# Power.net
KiCad netlist of a schematic drawn in Altium Designer
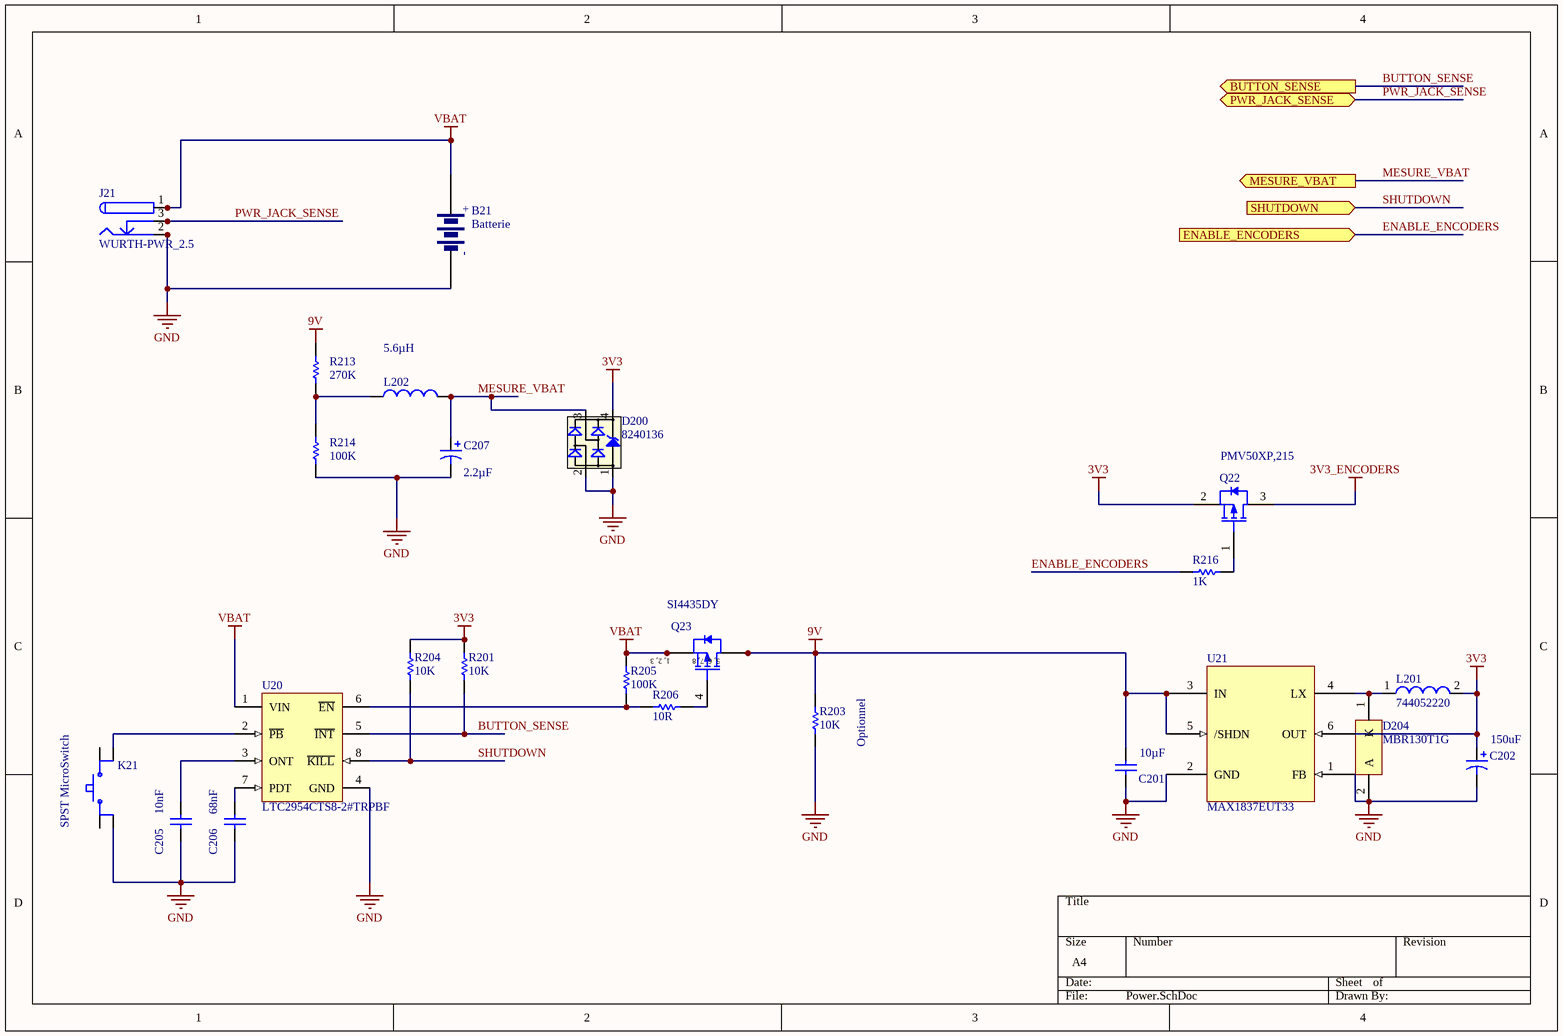
[diagram p0: Power.SchDoc]

(export (version "E")
  (design (tool "Eeschema 10.0.6"))
  (components
    (comp (ref "B21")
      (value "Batterie")
      (footprint "batterie")
      (description "Keystone 1294")
      (libsource (lib "Dumber 2015") (part "Batterie"))
    )
    (comp (ref "C201")
      (value "10µF")
      (footprint "CAPC1206(3216)100_L")
      (description "CAP 10µF 25V ±10% 1206 (3216 Metric) Thickness 1mm SMD")
      (fields (field (name "TOLERANCE") "Â±10%") (field (name "Comment") "CAP 10µF"))
      (libsource (lib "Altium Content Vault") (part "CMP-1037-01131-1"))
    )
    (comp (ref "C202")
      (value "150uF")
      (footprint "B")
      (description "CAP Tantalum, Body B, 150µF / 6.3V")
      (fields (field (name "Comment") "CAP 150µF") (field (name "PUBLISHER") "Altium Limited"))
      (libsource (lib "Vishay Sprague Tantalum Chip Capacitor") (part "194D225X0015B2"))
    )
    (comp (ref "C205")
      (value "10nF")
      (footprint "CAPC1206(3216)170_L")
      (description "CAP 100nF 50V ±10% 1206 (3216 Metric) Thickness 1.7mm SMD")
      (fields (field (name "TOLERANCE") "Â±10%") (field (name "Comment") "CAP 10nf"))
      (libsource (lib "Altium Content Vault") (part "CMP-1037-04201-1"))
    )
    (comp (ref "C206")
      (value "68nF")
      (footprint "CAPC1206(3216)170_L")
      (description "CAP 100nF 50V ±10% 1206 (3216 Metric) Thickness 1.7mm SMD")
      (fields (field (name "TOLERANCE") "Â±10%") (field (name "Comment") "CAP 68nF"))
      (libsource (lib "Altium Content Vault") (part "CMP-1037-04201-1"))
    )
    (comp (ref "C207")
      (value "2.2µF")
      (footprint "B")
      (description "Solid Tantalum Chip Capacitor, Standard T491 Series - Industrial Grade")
      (fields (field (name "Comment") "T491B") (field (name "PUBLISHER") "Altium Limited"))
      (libsource (lib "KEMET Chip Capacitor") (part "T491B"))
    )
    (comp (ref "D200")
      (value "8240136")
      (footprint "SOT143-4L")
      (description "TVS Diode WE-TVS-HS, VRWM=3.3V")
      (fields (field (name "MANUFACTURER") "Wuerth Elektronik"))
      (libsource (lib "Altium Content Vault") (part "WE-TVS-HS-4"))
    )
    (comp (ref "D204")
      (value "MBR130T1G")
      (footprint "ONSC-SOD-123-2-425-04_V")
      (description "Schottky Power Rectifier, 2-Pin SOD-123, Pb-Free, Tape and Reel")
      (fields (field (name "MANUFACTURER") "On Semiconductor"))
      (libsource (lib "Altium Content Vault") (part "CMP-1055-00423-1"))
    )
    (comp (ref "J21")
      (value "WURTH-PWR_2.5")
      (footprint "Wurth_2.5")
      (description "Low Voltage Power Supply Connector")
      (fields (field (name "PUBLISHER") "Altium Limited"))
      (libsource (lib "Dumber 2015") (part "WURTH-PWR_2.5"))
    )
    (comp (ref "K21")
      (value "SPST MicroSwitch")
      (footprint "SPST_MicroSwitch")
      (description "SPST - MicroSwitch")
      (libsource (lib "INSA") (part "SPST MicroSwitch"))
    )
    (comp (ref "L201")
      (value "744052220")
      (footprint "WE-TPC-5818-L")
      (description "SMD Shielded Tiny Power Inductor WE-TPC, L = 22.0 µH")
      (libsource (lib "Altium Content Vault") (part "CMP-0227-00400-1"))
    )
    (comp (ref "L202")
      (value "5.6µH")
      (footprint "1812")
      (description "Inductor SMD")
      (fields (field (name "Comment") "Inductor") (field (name "PUBLISHER") "Altium Limited"))
      (libsource (lib "INSA") (part "Inductor"))
    )
    (comp (ref "Q22")
      (value "PMV50XP,215")
      (footprint "NXP-SOT23_N")
      (description "Single P-Channel Trench MOSFET, -20 V, -55 to 150 degC, 3-Pin SOT23, Tape and Reel")
      (fields (field (name "PARTNUMBER") "PMV65XP,215") (field (name "MANUFACTURER") "NXP Semiconductors"))
      (libsource (lib "Altium Content Vault") (part "CMP-1258-00162-1"))
    )
    (comp (ref "Q23")
      (value "SI4435DY")
      (footprint "SO-8_N")
      (description "P-Channel 30V (D-S) Rated  MOSFET")
      (fields (field (name "PUBLISHER") "Altium Limited"))
      (libsource (lib "Vishay Siliconix Discrete MOSFET") (part "SI4435DY"))
    )
    (comp (ref "R201")
      (value "10K")
      (footprint "RESC1206(3216)_M")
      (description "10K 0.25W 5% 1206 (3216 Metric)  SMD")
      (fields (field (name "POWER") "0.25 W") (field (name "TOLERANCE") "5 %"))
      (libsource (lib "Altium Content Vault") (part "CMP-1014-00098-1"))
    )
    (comp (ref "R203")
      (value "10K")
      (footprint "RESC1206(3216)_M")
      (description "10K 0.25W 5% 1206 (3216 Metric)  SMD")
      (fields (field (name "POWER") "0.25 W") (field (name "TOLERANCE") "5 %"))
      (libsource (lib "Altium Content Vault") (part "CMP-1014-00098-1"))
    )
    (comp (ref "R204")
      (value "10K")
      (footprint "RESC1206(3216)_M")
      (description "10K 0.25W 5% 1206 (3216 Metric)  SMD")
      (fields (field (name "POWER") "0.25 W") (field (name "TOLERANCE") "5 %"))
      (libsource (lib "Altium Content Vault") (part "CMP-1014-00098-1"))
    )
    (comp (ref "R205")
      (value "100K")
      (footprint "RESC1206(3216)_M")
      (description "10K 0.25W 5% 1206 (3216 Metric)  SMD")
      (fields (field (name "POWER") "0.25 W") (field (name "TOLERANCE") "5 %"))
      (libsource (lib "Altium Content Vault") (part "CMP-1014-00098-1"))
    )
    (comp (ref "R206")
      (value "10R")
      (footprint "RESC1206(3216)_M")
      (description "10K 0.25W 5% 1206 (3216 Metric)  SMD")
      (fields (field (name "POWER") "0.25 W") (field (name "TOLERANCE") "5 %"))
      (libsource (lib "Altium Content Vault") (part "CMP-1014-00098-1"))
    )
    (comp (ref "R213")
      (value "270K")
      (footprint "RESC0805(2012)_M")
      (description "270K 0.125W 5% 0805 (2012 Metric)  SMD")
      (fields (field (name "TOLERANCE") "5 %") (field (name "POWER") "0.125 W"))
      (libsource (lib "Altium Content Vault") (part "CMP-1013-00132-1"))
    )
    (comp (ref "R214")
      (value "100K")
      (footprint "RESC1206(3216)_M")
      (description "10K 0.25W 5% 1206 (3216 Metric)  SMD")
      (fields (field (name "POWER") "0.25 W") (field (name "TOLERANCE") "5 %"))
      (libsource (lib "Altium Content Vault") (part "CMP-1014-00098-1"))
    )
    (comp (ref "R216")
      (value "1K")
      (footprint "RESC1206(3216)_M")
      (description "10K 0.25W 5% 1206 (3216 Metric)  SMD")
      (fields (field (name "POWER") "0.25 W") (field (name "TOLERANCE") "5 %"))
      (libsource (lib "Altium Content Vault") (part "CMP-1014-00098-1"))
    )
    (comp (ref "U20")
      (value "LTC2954CTS8-2#TRPBF")
      (footprint "LT-TS8-8-TSOT-23_V")
      (fields (field (name "MANUFACTURER") "Linear Technology"))
      (libsource (lib "Altium Content Vault") (part "LT-LTC2954-2-TS8-8"))
    )
    (comp (ref "U21") (value "MAX1837EUT33") (footprint "SOT23-6") (libsource (lib "INSA") (part "MAX1837")))
  )
  (nets
    (net (code "1") (name "/BUTTON_SENSE") (class "Default")
      (node (ref "R201") (pin "2") (pinfunction "2_2") (pintype "passive"))
      (node (ref "U20") (pin "5") (pinfunction "~{INT}_5") (pintype "open_collector"))
    )
    (net (code "2") (name "/ENABLE_ENCODERS") (class "Default")
      (node (ref "R216") (pin "2") (pinfunction "2_2") (pintype "passive"))
    )
    (net (code "3") (name "/MESURE_VBAT") (class "Default")
      (node (ref "C207") (pin "1") (pinfunction "1_1") (pintype "passive"))
      (node (ref "D200") (pin "3") (pinfunction "I/O2_3") (pintype "passive"))
      (node (ref "L202") (pin "2") (pinfunction "2_2") (pintype "passive"))
    )
    (net (code "4") (name "/PWR_JACK_SENSE") (class "Default")
      (node (ref "J21") (pin "3") (pinfunction "3_3") (pintype "power_in"))
      (node (ref "J21") (pin "3A") (pinfunction "3A_3A") (pintype "power_in"))
      (node (ref "J21") (pin "3B") (pinfunction "3B_3B") (pintype "power_in"))
    )
    (net (code "5") (name "/SHUTDOWN") (class "Default")
      (node (ref "R204") (pin "2") (pinfunction "2_2") (pintype "passive"))
      (node (ref "U20") (pin "8") (pinfunction "~{KILL}_8") (pintype "input"))
    )
    (net (code "6") (name "3V3") (class "Default")
      (node (ref "C202") (pin "1") (pinfunction "1_1") (pintype "passive"))
      (node (ref "D200") (pin "4") (pinfunction "VDD_4") (pintype "passive"))
      (node (ref "L201") (pin "2") (pinfunction "2_2") (pintype "passive"))
      (node (ref "Q22") (pin "2") (pinfunction "S_2") (pintype "passive"))
      (node (ref "R201") (pin "1") (pinfunction "1_1") (pintype "passive"))
      (node (ref "R204") (pin "1") (pinfunction "1_1") (pintype "passive"))
      (node (ref "U21") (pin "6") (pinfunction "OUT_6") (pintype "input"))
    )
    (net (code "7") (name "3V3_ENCODERS") (class "Default")
      (node (ref "Q22") (pin "3") (pinfunction "D_3") (pintype "passive"))
    )
    (net (code "8") (name "9V") (class "Default")
      (node (ref "C201") (pin "2") (pinfunction "2_2") (pintype "passive"))
      (node (ref "Q23") (pin "5") (pinfunction "D_5") (pintype "passive"))
      (node (ref "Q23") (pin "6") (pinfunction "D_6") (pintype "passive"))
      (node (ref "Q23") (pin "7") (pinfunction "D_7") (pintype "passive"))
      (node (ref "Q23") (pin "8") (pinfunction "D_8") (pintype "passive"))
      (node (ref "R203") (pin "1") (pinfunction "1_1") (pintype "passive"))
      (node (ref "R213") (pin "2") (pinfunction "2_2") (pintype "passive"))
      (node (ref "U21") (pin "3") (pinfunction "IN_3") (pintype "power_in"))
      (node (ref "U21") (pin "5") (pinfunction "/SHDN_5") (pintype "input"))
    )
    (net (code "9") (name "GND") (class "Default")
      (node (ref "B21") (pin "V-") (pinfunction "V-_V-") (pintype "passive"))
      (node (ref "C201") (pin "1") (pinfunction "1_1") (pintype "passive"))
      (node (ref "C202") (pin "2") (pinfunction "2_2") (pintype "passive"))
      (node (ref "C205") (pin "1") (pinfunction "1_1") (pintype "passive"))
      (node (ref "C206") (pin "1") (pinfunction "1_1") (pintype "passive"))
      (node (ref "C207") (pin "2") (pinfunction "2_2") (pintype "passive"))
      (node (ref "D200") (pin "1") (pinfunction "GND_1") (pintype "passive"))
      (node (ref "D200") (pin "2") (pinfunction "I/O1_2") (pintype "passive"))
      (node (ref "D204") (pin "2") (pinfunction "A_2") (pintype "passive"))
      (node (ref "J21") (pin "2") (pinfunction "2_2") (pintype "power_in"))
      (node (ref "J21") (pin "2A") (pinfunction "2A_2A") (pintype "power_in"))
      (node (ref "J21") (pin "2B") (pinfunction "2B_2B") (pintype "power_in"))
      (node (ref "K21") (pin "2") (pinfunction "2_2") (pintype "passive"))
      (node (ref "R203") (pin "2") (pinfunction "2_2") (pintype "passive"))
      (node (ref "R214") (pin "2") (pinfunction "2_2") (pintype "passive"))
      (node (ref "U20") (pin "4") (pinfunction "GND_4") (pintype "power_in"))
      (node (ref "U21") (pin "1") (pinfunction "FB_1") (pintype "input"))
      (node (ref "U21") (pin "2") (pinfunction "GND_2") (pintype "power_in"))
    )
    (net (code "10") (name "Net-(D204-K)") (class "Default")
      (node (ref "D204") (pin "1") (pinfunction "K_1") (pintype "passive"))
      (node (ref "L201") (pin "1") (pinfunction "1_1") (pintype "passive"))
      (node (ref "U21") (pin "4") (pinfunction "LX_4") (pintype "power_in"))
    )
    (net (code "11") (name "Net-(L202-Pad1)") (class "Default")
      (node (ref "L202") (pin "1") (pinfunction "1_1") (pintype "passive"))
      (node (ref "R213") (pin "1") (pinfunction "1_1") (pintype "passive"))
      (node (ref "R214") (pin "1") (pinfunction "1_1") (pintype "passive"))
    )
    (net (code "12") (name "Net-(Q22-G)") (class "Default")
      (node (ref "Q22") (pin "1") (pinfunction "G_1") (pintype "passive"))
      (node (ref "R216") (pin "1") (pinfunction "1_1") (pintype "passive"))
    )
    (net (code "13") (name "Net-(Q23-G)") (class "Default")
      (node (ref "Q23") (pin "4") (pinfunction "G_4") (pintype "passive"))
      (node (ref "R206") (pin "1") (pinfunction "1_1") (pintype "passive"))
    )
    (net (code "14") (name "Net-(U20-ONT)") (class "Default")
      (node (ref "C205") (pin "2") (pinfunction "2_2") (pintype "passive"))
      (node (ref "U20") (pin "3") (pinfunction "ONT_3") (pintype "input"))
    )
    (net (code "15") (name "Net-(U20-PDT)") (class "Default")
      (node (ref "C206") (pin "2") (pinfunction "2_2") (pintype "passive"))
      (node (ref "U20") (pin "7") (pinfunction "PDT_7") (pintype "input"))
    )
    (net (code "16") (name "Net-(U20-~{EN})") (class "Default")
      (node (ref "R205") (pin "2") (pinfunction "2_2") (pintype "passive"))
      (node (ref "R206") (pin "2") (pinfunction "2_2") (pintype "passive"))
      (node (ref "U20") (pin "6") (pinfunction "~{EN}_6") (pintype "open_collector"))
    )
    (net (code "17") (name "Net-(U20-~{PB})") (class "Default")
      (node (ref "K21") (pin "4") (pinfunction "4_4") (pintype "passive"))
      (node (ref "U20") (pin "2") (pinfunction "~{PB}_2") (pintype "input"))
    )
    (net (code "18") (name "VBAT") (class "Default")
      (node (ref "B21") (pin "V+") (pinfunction "V+_V+") (pintype "passive"))
      (node (ref "J21") (pin "1") (pinfunction "1_1") (pintype "power_in"))
      (node (ref "J21") (pin "1A") (pinfunction "1A_1A") (pintype "power_in"))
      (node (ref "J21") (pin "1B") (pinfunction "1B_1B") (pintype "power_in"))
      (node (ref "Q23") (pin "1") (pinfunction "S_1") (pintype "passive"))
      (node (ref "Q23") (pin "2") (pinfunction "S_2") (pintype "passive"))
      (node (ref "Q23") (pin "3") (pinfunction "S_3") (pintype "passive"))
      (node (ref "R205") (pin "1") (pinfunction "1_1") (pintype "passive"))
      (node (ref "U20") (pin "1") (pinfunction "VIN_1") (pintype "power_in"))
    )
    (net (code "19") (name "unconnected-(K21-Pad1)") (class "Default")
      (node (ref "K21") (pin "1") (pinfunction "1_1") (pintype "passive"))
    )
    (net (code "20") (name "unconnected-(K21-Pad3)") (class "Default")
      (node (ref "K21") (pin "3") (pinfunction "3_3") (pintype "passive"))
    )
  )
)
